# power_xt60_frontpanel.net
KiCad netlist of a schematic drawn in EAGLE
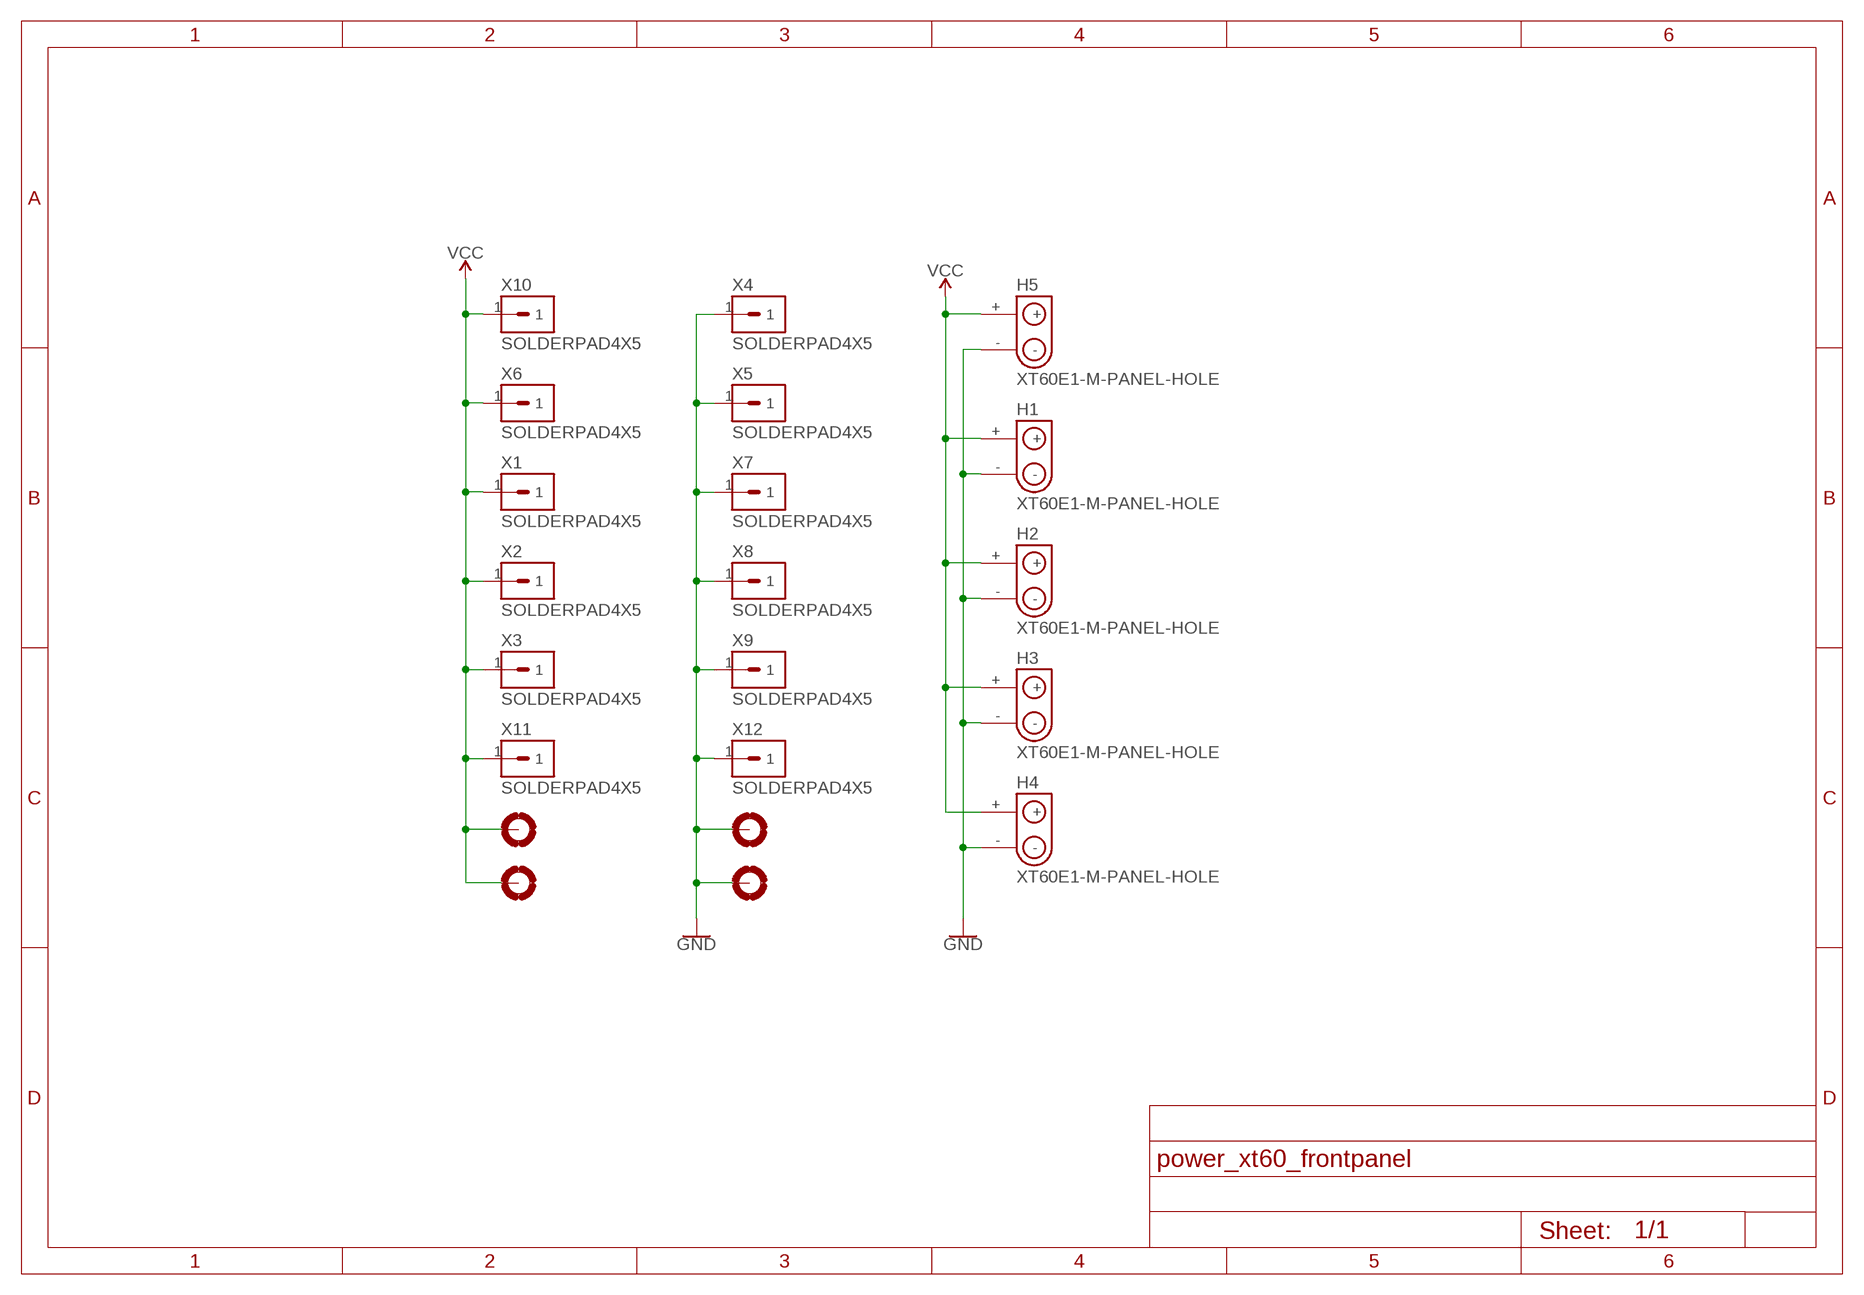
[diagram p0: schematic, sheet 1]

(export (version "E")
  (design (tool "Eeschema 10.0.6"))
  (components
    (comp (ref "H1")
      (value "XT60E1-M-PANEL-HOLE")
      (footprint "eagle-import:XT60E1-M-PANEL-HOLE")
      (libsource (lib "eagle-import") (part "XT60E1-M-PANEL-HOLE"))
    )
    (comp (ref "H2")
      (value "XT60E1-M-PANEL-HOLE")
      (footprint "eagle-import:XT60E1-M-PANEL-HOLE")
      (libsource (lib "eagle-import") (part "XT60E1-M-PANEL-HOLE"))
    )
    (comp (ref "H3")
      (value "XT60E1-M-PANEL-HOLE")
      (footprint "eagle-import:XT60E1-M-PANEL-HOLE")
      (libsource (lib "eagle-import") (part "XT60E1-M-PANEL-HOLE"))
    )
    (comp (ref "H4")
      (value "XT60E1-M-PANEL-HOLE")
      (footprint "eagle-import:XT60E1-M-PANEL-HOLE")
      (libsource (lib "eagle-import") (part "XT60E1-M-PANEL-HOLE"))
    )
    (comp (ref "H5")
      (value "XT60E1-M-PANEL-HOLE")
      (footprint "eagle-import:XT60E1-M-PANEL-HOLE")
      (libsource (lib "eagle-import") (part "XT60E1-M-PANEL-HOLE"))
    )
    (comp (ref "H6")
      (value "MOUNTHOLE-PAD3.2")
      (footprint "eagle-import:3.2-PAD")
      (libsource (lib "eagle-import") (part "MOUNTHOLE-PAD3.2"))
    )
    (comp (ref "H7")
      (value "MOUNTHOLE-PAD3.2")
      (footprint "eagle-import:3.2-PAD")
      (libsource (lib "eagle-import") (part "MOUNTHOLE-PAD3.2"))
    )
    (comp (ref "H8")
      (value "MOUNTHOLE-PAD3.2")
      (footprint "eagle-import:3.2-PAD")
      (libsource (lib "eagle-import") (part "MOUNTHOLE-PAD3.2"))
    )
    (comp (ref "H9")
      (value "MOUNTHOLE-PAD3.2")
      (footprint "eagle-import:3.2-PAD")
      (libsource (lib "eagle-import") (part "MOUNTHOLE-PAD3.2"))
    )
    (comp (ref "X1")
      (value "SOLDERPAD4X5")
      (footprint "eagle-import:SOLDERPAD-4X5")
      (libsource (lib "eagle-import") (part "SOLDERPAD4X5"))
    )
    (comp (ref "X2")
      (value "SOLDERPAD4X5")
      (footprint "eagle-import:SOLDERPAD-4X5")
      (libsource (lib "eagle-import") (part "SOLDERPAD4X5"))
    )
    (comp (ref "X3")
      (value "SOLDERPAD4X5")
      (footprint "eagle-import:SOLDERPAD-4X5")
      (libsource (lib "eagle-import") (part "SOLDERPAD4X5"))
    )
    (comp (ref "X4")
      (value "SOLDERPAD4X5")
      (footprint "eagle-import:SOLDERPAD-4X5")
      (libsource (lib "eagle-import") (part "SOLDERPAD4X5"))
    )
    (comp (ref "X5")
      (value "SOLDERPAD4X5")
      (footprint "eagle-import:SOLDERPAD-4X5")
      (libsource (lib "eagle-import") (part "SOLDERPAD4X5"))
    )
    (comp (ref "X6")
      (value "SOLDERPAD4X5")
      (footprint "eagle-import:SOLDERPAD-4X5")
      (libsource (lib "eagle-import") (part "SOLDERPAD4X5"))
    )
    (comp (ref "X7")
      (value "SOLDERPAD4X5")
      (footprint "eagle-import:SOLDERPAD-4X5")
      (libsource (lib "eagle-import") (part "SOLDERPAD4X5"))
    )
    (comp (ref "X8")
      (value "SOLDERPAD4X5")
      (footprint "eagle-import:SOLDERPAD-4X5")
      (libsource (lib "eagle-import") (part "SOLDERPAD4X5"))
    )
    (comp (ref "X9")
      (value "SOLDERPAD4X5")
      (footprint "eagle-import:SOLDERPAD-4X5")
      (libsource (lib "eagle-import") (part "SOLDERPAD4X5"))
    )
    (comp (ref "X10")
      (value "SOLDERPAD4X5")
      (footprint "eagle-import:SOLDERPAD-4X5")
      (libsource (lib "eagle-import") (part "SOLDERPAD4X5"))
    )
    (comp (ref "X11")
      (value "SOLDERPAD4X5")
      (footprint "eagle-import:SOLDERPAD-4X5")
      (libsource (lib "eagle-import") (part "SOLDERPAD4X5"))
    )
    (comp (ref "X12")
      (value "SOLDERPAD4X5")
      (footprint "eagle-import:SOLDERPAD-4X5")
      (libsource (lib "eagle-import") (part "SOLDERPAD4X5"))
    )
  )
  (nets
    (net (code "1") (name "GND") (class "Default")
      (node (ref "H1") (pin "-") (pinfunction "-_-") (pintype "bidirectional"))
      (node (ref "H2") (pin "-") (pinfunction "-_-") (pintype "bidirectional"))
      (node (ref "H3") (pin "-") (pinfunction "-_-") (pintype "bidirectional"))
      (node (ref "H4") (pin "-") (pinfunction "-_-") (pintype "bidirectional"))
      (node (ref "H5") (pin "-") (pinfunction "-_-") (pintype "bidirectional"))
      (node (ref "H8") (pin "B3,2") (pinfunction "MOUNT_B3,2") (pintype "passive"))
      (node (ref "H9") (pin "B3,2") (pinfunction "MOUNT_B3,2") (pintype "passive"))
      (node (ref "X12") (pin "1") (pinfunction "1_1") (pintype "passive"))
      (node (ref "X4") (pin "1") (pinfunction "1_1") (pintype "passive"))
      (node (ref "X5") (pin "1") (pinfunction "1_1") (pintype "passive"))
      (node (ref "X7") (pin "1") (pinfunction "1_1") (pintype "passive"))
      (node (ref "X8") (pin "1") (pinfunction "1_1") (pintype "passive"))
      (node (ref "X9") (pin "1") (pinfunction "1_1") (pintype "passive"))
    )
    (net (code "2") (name "VCC") (class "Default")
      (node (ref "H1") (pin "+") (pinfunction "+_+") (pintype "bidirectional"))
      (node (ref "H2") (pin "+") (pinfunction "+_+") (pintype "bidirectional"))
      (node (ref "H3") (pin "+") (pinfunction "+_+") (pintype "bidirectional"))
      (node (ref "H4") (pin "+") (pinfunction "+_+") (pintype "bidirectional"))
      (node (ref "H5") (pin "+") (pinfunction "+_+") (pintype "bidirectional"))
      (node (ref "H6") (pin "B3,2") (pinfunction "MOUNT_B3,2") (pintype "passive"))
      (node (ref "H7") (pin "B3,2") (pinfunction "MOUNT_B3,2") (pintype "passive"))
      (node (ref "X1") (pin "1") (pinfunction "1_1") (pintype "passive"))
      (node (ref "X10") (pin "1") (pinfunction "1_1") (pintype "passive"))
      (node (ref "X11") (pin "1") (pinfunction "1_1") (pintype "passive"))
      (node (ref "X2") (pin "1") (pinfunction "1_1") (pintype "passive"))
      (node (ref "X3") (pin "1") (pinfunction "1_1") (pintype "passive"))
      (node (ref "X6") (pin "1") (pinfunction "1_1") (pintype "passive"))
    )
  )
)
